# Sch_Master_Screen.net
KiCad netlist of a schematic drawn in Altium Designer
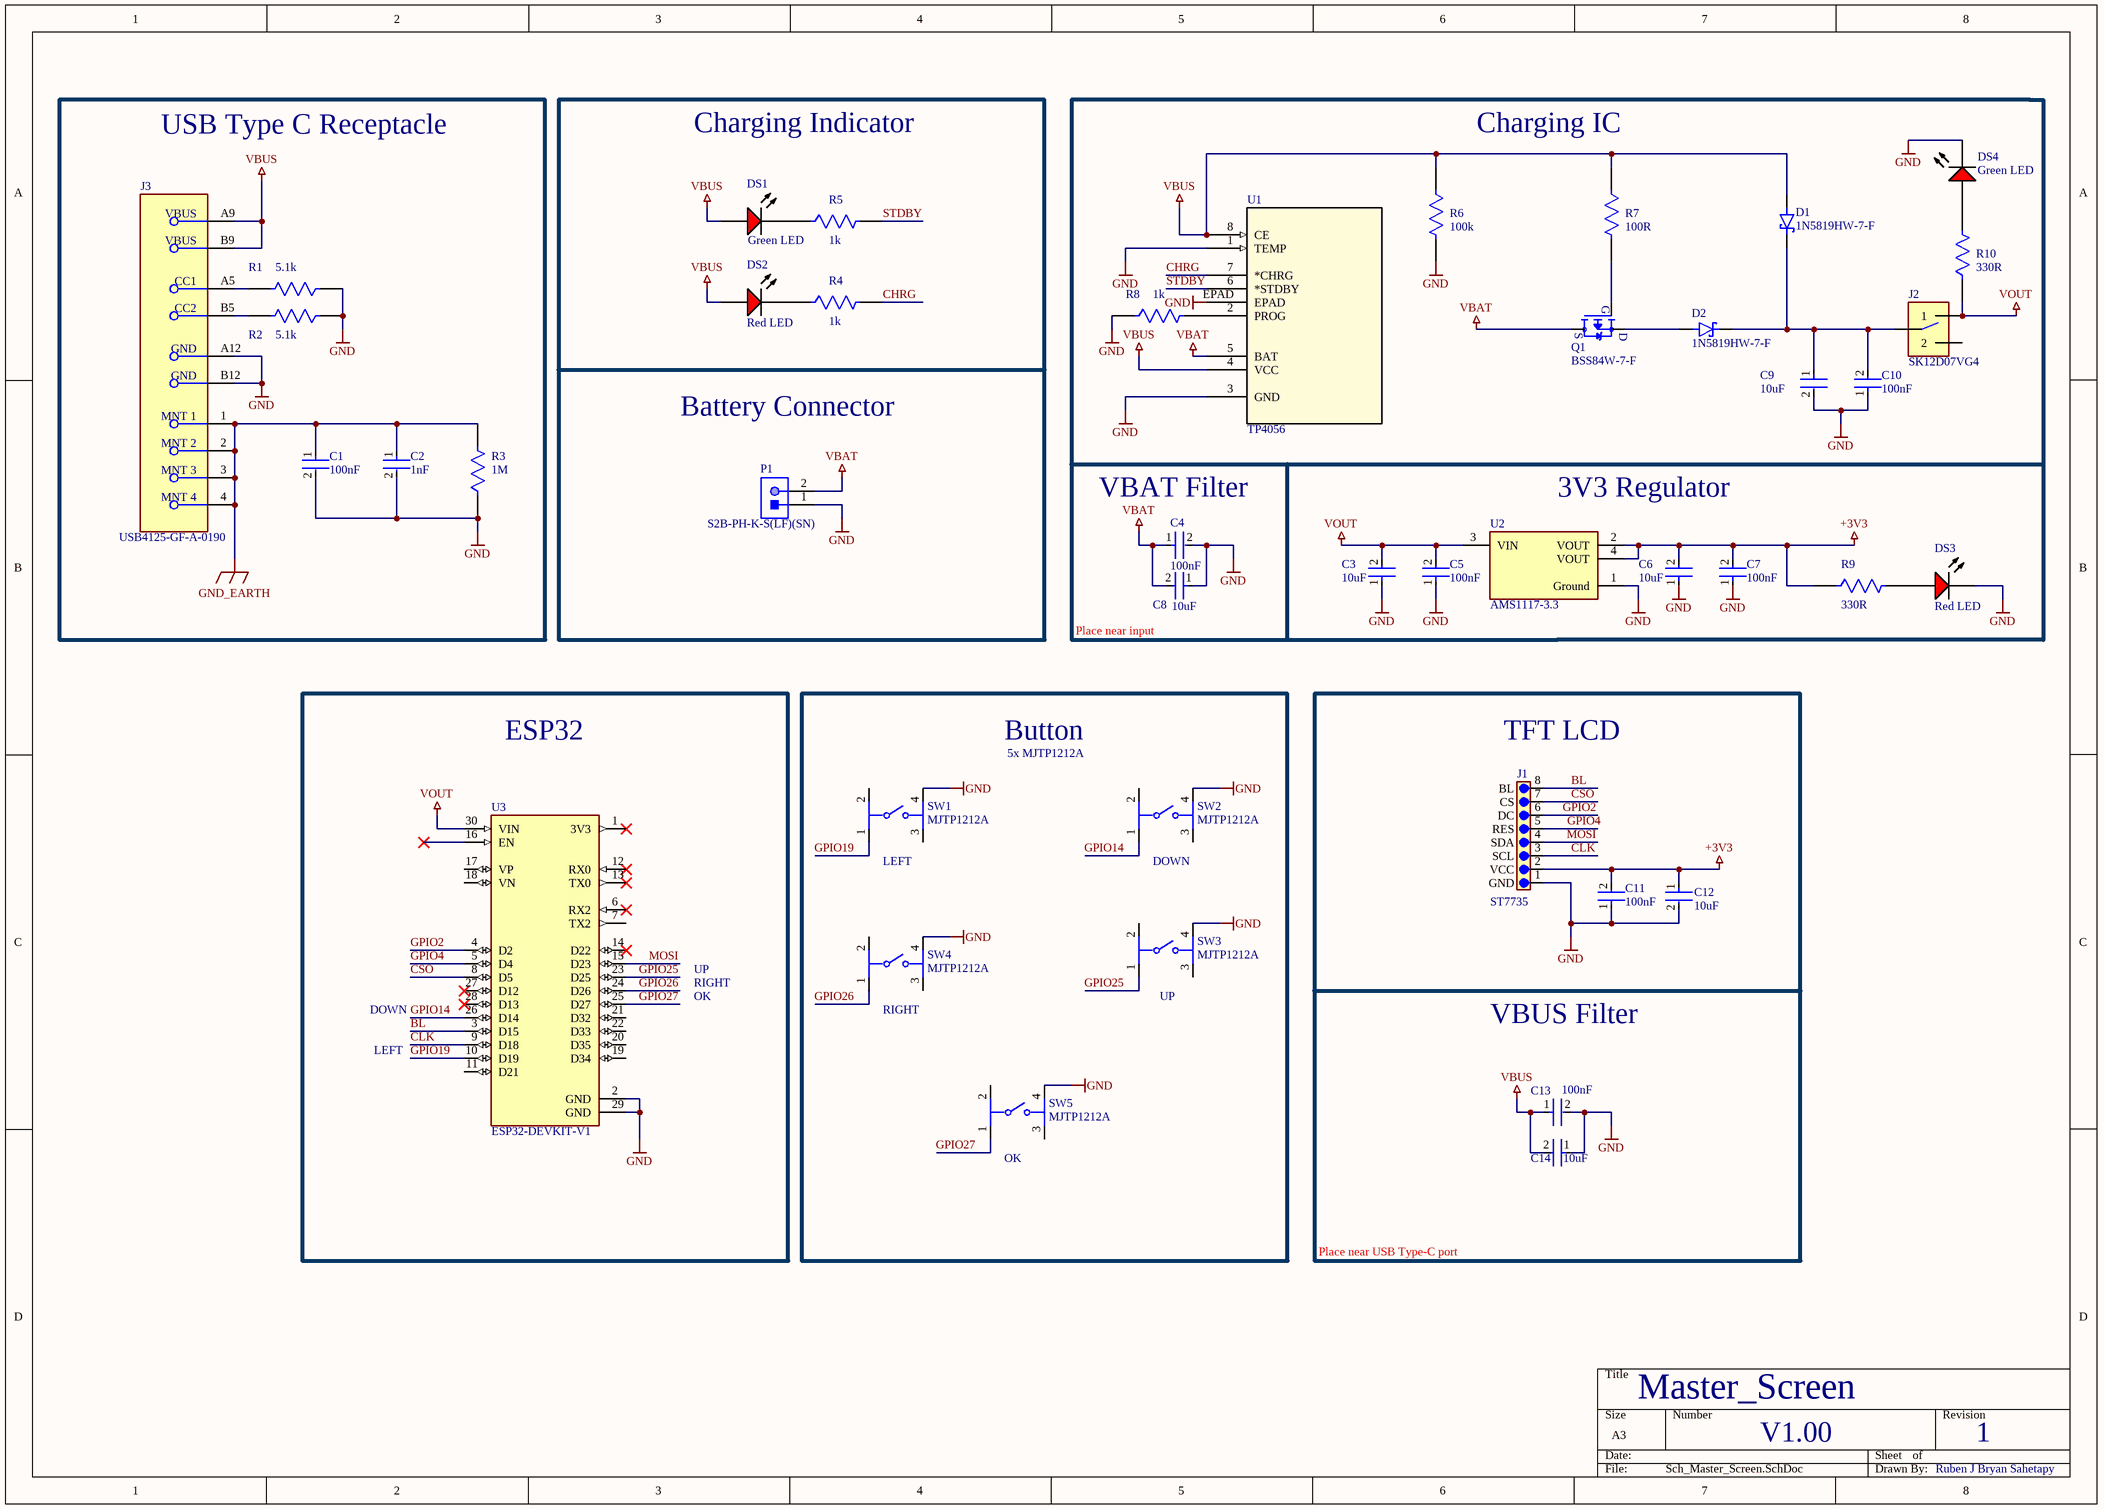
[diagram p0: Sch_Master_Screen.SchDoc]

(export (version "E")
  (design (tool "Eeschema 10.0.6"))
  (components
    (comp (ref "C1")
      (value "100nF")
      (footprint "FP-CC0805-0_85-MFG")
      (description "CAP CER 0.1UF 16V X7R 0805")
      (fields
        (field (name "MANUFACTURER PART NUMBER") "CC0805KRX7R7BB104")
        (field (name "MANUFACTURER") "Yageo")
      )
      (libsource (lib "Altium Content Vault") (part "11868f565c42a9108669ba33697ecf6"))
    )
    (comp (ref "C2")
      (value "1nF")
      (footprint "FP-CC0805-0_85-MFG")
      (description "CAP CER 0.1UF 16V X7R 0805")
      (fields
        (field (name "MANUFACTURER PART NUMBER") "CC0805KRX7R7BB104")
        (field (name "MANUFACTURER") "Yageo")
      )
      (libsource (lib "Altium Content Vault") (part "11868f565c42a9108669ba33697ecf6"))
    )
    (comp (ref "C3")
      (value "10uF")
      (footprint "FP-CC0805-0_85-MFG")
      (description "CAP CER 0.1UF 16V X7R 0805")
      (fields
        (field (name "MANUFACTURER PART NUMBER") "CC0805KRX7R7BB104")
        (field (name "MANUFACTURER") "Yageo")
      )
      (libsource (lib "Altium Content Vault") (part "11868f565c42a9108669ba33697ecf6"))
    )
    (comp (ref "C4")
      (value "100nF")
      (footprint "FP-CC0805-0_85-MFG")
      (description "CAP CER 0.1UF 16V X7R 0805")
      (fields
        (field (name "MANUFACTURER PART NUMBER") "CC0805KRX7R7BB104")
        (field (name "MANUFACTURER") "Yageo")
      )
      (libsource (lib "Altium Content Vault") (part "11868f565c42a9108669ba33697ecf6"))
    )
    (comp (ref "C5")
      (value "100nF")
      (footprint "FP-CC0805-0_85-MFG")
      (description "CAP CER 0.1UF 16V X7R 0805")
      (fields
        (field (name "MANUFACTURER PART NUMBER") "CC0805KRX7R7BB104")
        (field (name "MANUFACTURER") "Yageo")
      )
      (libsource (lib "Altium Content Vault") (part "11868f565c42a9108669ba33697ecf6"))
    )
    (comp (ref "C6")
      (value "10uF")
      (footprint "FP-CC0805-0_85-MFG")
      (description "CAP CER 0.1UF 16V X7R 0805")
      (fields
        (field (name "MANUFACTURER PART NUMBER") "CC0805KRX7R7BB104")
        (field (name "MANUFACTURER") "Yageo")
      )
      (libsource (lib "Altium Content Vault") (part "11868f565c42a9108669ba33697ecf6"))
    )
    (comp (ref "C7")
      (value "100nF")
      (footprint "FP-CC0805-0_85-MFG")
      (description "CAP CER 0.1UF 16V X7R 0805")
      (fields
        (field (name "MANUFACTURER PART NUMBER") "CC0805KRX7R7BB104")
        (field (name "MANUFACTURER") "Yageo")
      )
      (libsource (lib "Altium Content Vault") (part "11868f565c42a9108669ba33697ecf6"))
    )
    (comp (ref "C8")
      (value "10uF")
      (footprint "FP-CC0805-0_85-MFG")
      (description "CAP CER 0.1UF 16V X7R 0805")
      (fields
        (field (name "MANUFACTURER PART NUMBER") "CC0805KRX7R7BB104")
        (field (name "MANUFACTURER") "Yageo")
      )
      (libsource (lib "Altium Content Vault") (part "11868f565c42a9108669ba33697ecf6"))
    )
    (comp (ref "C9")
      (value "10uF")
      (footprint "FP-CC0805-0_85-MFG")
      (description "CAP CER 0.1UF 16V X7R 0805")
      (fields
        (field (name "MANUFACTURER PART NUMBER") "CC0805KRX7R7BB104")
        (field (name "MANUFACTURER") "Yageo")
      )
      (libsource (lib "Altium Content Vault") (part "11868f565c42a9108669ba33697ecf6"))
    )
    (comp (ref "C10")
      (value "100nF")
      (footprint "FP-CC0805-0_85-MFG")
      (description "CAP CER 0.1UF 16V X7R 0805")
      (fields
        (field (name "MANUFACTURER PART NUMBER") "CC0805KRX7R7BB104")
        (field (name "MANUFACTURER") "Yageo")
      )
      (libsource (lib "Altium Content Vault") (part "11868f565c42a9108669ba33697ecf6"))
    )
    (comp (ref "C11")
      (value "100nF")
      (footprint "FP-CC0805-0_85-MFG")
      (description "CAP CER 0.1UF 16V X7R 0805")
      (fields
        (field (name "MANUFACTURER PART NUMBER") "CC0805KRX7R7BB104")
        (field (name "MANUFACTURER") "Yageo")
      )
      (libsource (lib "Altium Content Vault") (part "11868f565c42a9108669ba33697ecf6"))
    )
    (comp (ref "C12")
      (value "10uF")
      (footprint "FP-CC0805-0_85-MFG")
      (description "CAP CER 0.1UF 16V X7R 0805")
      (fields
        (field (name "MANUFACTURER PART NUMBER") "CC0805KRX7R7BB104")
        (field (name "MANUFACTURER") "Yageo")
      )
      (libsource (lib "Altium Content Vault") (part "11868f565c42a9108669ba33697ecf6"))
    )
    (comp (ref "C13")
      (value "100nF")
      (footprint "FP-CC0805-0_85-MFG")
      (description "CAP CER 0.1UF 16V X7R 0805")
      (fields
        (field (name "MANUFACTURER PART NUMBER") "CC0805KRX7R7BB104")
        (field (name "MANUFACTURER") "Yageo")
      )
      (libsource (lib "Altium Content Vault") (part "11868f565c42a9108669ba33697ecf6"))
    )
    (comp (ref "C14")
      (value "10uF")
      (footprint "FP-CC0805-0_85-MFG")
      (description "CAP CER 0.1UF 16V X7R 0805")
      (fields
        (field (name "MANUFACTURER PART NUMBER") "CC0805KRX7R7BB104")
        (field (name "MANUFACTURER") "Yageo")
      )
      (libsource (lib "Altium Content Vault") (part "11868f565c42a9108669ba33697ecf6"))
    )
    (comp (ref "D1")
      (value "1N5819HW-7-F")
      (footprint "SOD3715X145N")
      (description "Schottky Diodes & Rectifiers SOD-123")
      (fields (field (name "MF") "Diodes Inc."))
      (libsource (lib "MarbleLib") (part "1N5819HW-7-F"))
    )
    (comp (ref "D2")
      (value "1N5819HW-7-F")
      (footprint "SOD3715X145N")
      (description "Schottky Diodes & Rectifiers SOD-123")
      (fields (field (name "MF") "Diodes Inc."))
      (libsource (lib "MarbleLib") (part "1N5819HW-7-F"))
    )
    (comp (ref "DS1")
      (value "Green LED")
      (footprint "LUMX-SML-LX1206IC_V")
      (description "LED Red, 65 mW, -40 to 85 degC, 2-Pin SMD, RoHS, Tape and Reel")
      (fields (field (name "MANUFACTURER") "Lumex") (field (name "PART NO") "SML-LX1206IC-TR"))
      (libsource (lib "Altium Content Vault") (part "LED-RED-AK-2"))
    )
    (comp (ref "DS2")
      (value "Red LED")
      (footprint "LUMX-SML-LX1206IC_V")
      (description "LED Red, 65 mW, -40 to 85 degC, 2-Pin SMD, RoHS, Tape and Reel")
      (fields (field (name "MANUFACTURER") "Lumex") (field (name "PART NO") "SML-LX1206IC-TR"))
      (libsource (lib "Altium Content Vault") (part "LED-RED-AK-2"))
    )
    (comp (ref "DS3")
      (value "Red LED")
      (footprint "LUMX-SML-LX1206IC_V")
      (description "LED Red, 65 mW, -40 to 85 degC, 2-Pin SMD, RoHS, Tape and Reel")
      (fields (field (name "MANUFACTURER") "Lumex") (field (name "PART NO") "SML-LX1206IC-TR"))
      (libsource (lib "Altium Content Vault") (part "LED-RED-AK-2"))
    )
    (comp (ref "DS4")
      (value "Green LED")
      (footprint "LUMX-SML-LX1206IC_V")
      (description "LED Red, 65 mW, -40 to 85 degC, 2-Pin SMD, RoHS, Tape and Reel")
      (fields (field (name "MANUFACTURER") "Lumex") (field (name "PART NO") "SML-LX1206IC-TR"))
      (libsource (lib "Altium Content Vault") (part "LED-RED-AK-2"))
    )
    (comp (ref "J1")
      (value "ST7735")
      (footprint "ST7735")
      (description "1.8 inches 128x160 RGB TFT LCD - ST7735 DRIVER")
      (fields (field (name "PART NUMBER") "TFT-ST7735"))
      (libsource (lib "MarbleLib") (part "ST7735"))
    )
    (comp (ref "J2")
      (value "SK12D07VG4")
      (footprint "SK12D07VG4")
      (description "Slide Switches - Side Knob")
      (fields (field (name "MF") "C&K"))
      (libsource (lib "MarbleLib") (part "SK12D07VG4"))
    )
    (comp (ref "J3")
      (value "USB4125-GF-A-0190")
      (footprint "FP-USB4125-GF-A-0190-MFG")
      (description "CONN RCPT TYPE C 6P SMD RA")
      (libsource (lib "Altium Content Vault") (part "a055484d46e58b234844902c9fd883a"))
    )
    (comp (ref "P1")
      (value "S2B-PH-K-S(LF)(SN)")
      (footprint "JST-S2B-PH-K-S_V")
      (fields (field (name "TOLERANCE") "20%"))
      (libsource (lib "Altium Content Vault") (part "CN-1P-M-R2"))
    )
    (comp (ref "Q1")
      (value "BSS84W-7-F")
      (footprint "SOT65P222X110-3N")
      (description "MOSFET P-Channel 50V 130MA SOT323")
      (fields (field (name "MF") "Diodes Inc."))
      (libsource (lib "MarbleLib") (part "BSS84W-7-F"))
    )
    (comp (ref "R1")
      (value "5.1k")
      (footprint "FP-RC1206-MFG")
      (description "RES SMD 0 OHM JUMPER 1/4W 1206")
      (fields
        (field (name "MANUFACTURER PART NUMBER") "RC1206JR-070RL")
        (field (name "MANUFACTURER") "YAGEO")
      )
      (libsource (lib "Altium Content Vault") (part "1029c3af85768c4190bb7ad29bc67b5"))
    )
    (comp (ref "R2")
      (value "5.1k")
      (footprint "FP-RC1206-MFG")
      (description "RES SMD 0 OHM JUMPER 1/4W 1206")
      (fields
        (field (name "MANUFACTURER PART NUMBER") "RC1206JR-070RL")
        (field (name "MANUFACTURER") "YAGEO")
      )
      (libsource (lib "Altium Content Vault") (part "1029c3af85768c4190bb7ad29bc67b5"))
    )
    (comp (ref "R3")
      (value "1M")
      (footprint "FP-RC1206-MFG")
      (description "RES SMD 0 OHM JUMPER 1/4W 1206")
      (fields
        (field (name "MANUFACTURER PART NUMBER") "RC1206JR-070RL")
        (field (name "MANUFACTURER") "YAGEO")
      )
      (libsource (lib "Altium Content Vault") (part "1029c3af85768c4190bb7ad29bc67b5"))
    )
    (comp (ref "R4")
      (value "1k")
      (footprint "FP-RC1206-MFG")
      (description "RES SMD 0 OHM JUMPER 1/4W 1206")
      (fields
        (field (name "MANUFACTURER PART NUMBER") "RC1206JR-070RL")
        (field (name "MANUFACTURER") "YAGEO")
      )
      (libsource (lib "Altium Content Vault") (part "1029c3af85768c4190bb7ad29bc67b5"))
    )
    (comp (ref "R5")
      (value "1k")
      (footprint "FP-RC1206-MFG")
      (description "RES SMD 0 OHM JUMPER 1/4W 1206")
      (fields
        (field (name "MANUFACTURER PART NUMBER") "RC1206JR-070RL")
        (field (name "MANUFACTURER") "YAGEO")
      )
      (libsource (lib "Altium Content Vault") (part "1029c3af85768c4190bb7ad29bc67b5"))
    )
    (comp (ref "R6")
      (value "100k")
      (footprint "FP-RC1206-MFG")
      (description "RES SMD 0 OHM JUMPER 1/4W 1206")
      (fields
        (field (name "MANUFACTURER PART NUMBER") "RC1206JR-070RL")
        (field (name "MANUFACTURER") "YAGEO")
      )
      (libsource (lib "Altium Content Vault") (part "1029c3af85768c4190bb7ad29bc67b5"))
    )
    (comp (ref "R7")
      (value "100R")
      (footprint "FP-RC1206-MFG")
      (description "RES SMD 0 OHM JUMPER 1/4W 1206")
      (fields
        (field (name "MANUFACTURER PART NUMBER") "RC1206JR-070RL")
        (field (name "MANUFACTURER") "YAGEO")
      )
      (libsource (lib "Altium Content Vault") (part "1029c3af85768c4190bb7ad29bc67b5"))
    )
    (comp (ref "R8")
      (value "1k")
      (footprint "FP-RC1206-MFG")
      (description "RES SMD 0 OHM JUMPER 1/4W 1206")
      (fields
        (field (name "MANUFACTURER PART NUMBER") "RC1206JR-070RL")
        (field (name "MANUFACTURER") "YAGEO")
      )
      (libsource (lib "Altium Content Vault") (part "1029c3af85768c4190bb7ad29bc67b5"))
    )
    (comp (ref "R9")
      (value "330R")
      (footprint "FP-RC1206-MFG")
      (description "RES SMD 0 OHM JUMPER 1/4W 1206")
      (fields
        (field (name "MANUFACTURER PART NUMBER") "RC1206JR-070RL")
        (field (name "MANUFACTURER") "YAGEO")
      )
      (libsource (lib "Altium Content Vault") (part "1029c3af85768c4190bb7ad29bc67b5"))
    )
    (comp (ref "R10")
      (value "330R")
      (footprint "FP-RC1206-MFG")
      (description "RES SMD 0 OHM JUMPER 1/4W 1206")
      (fields
        (field (name "MANUFACTURER PART NUMBER") "RC1206JR-070RL")
        (field (name "MANUFACTURER") "YAGEO")
      )
      (libsource (lib "Altium Content Vault") (part "1029c3af85768c4190bb7ad29bc67b5"))
    )
    (comp (ref "SW1")
      (value "MJTP1212A")
      (footprint "FP-MJTP1212A-MFG")
      (description "Switch Tactile Button 12x12mm")
      (libsource (lib "MarbleLib") (part "CMP-47024-000003-1"))
    )
    (comp (ref "SW2")
      (value "MJTP1212A")
      (footprint "FP-MJTP1212A-MFG")
      (description "Switch Tactile Button 12x12mm")
      (libsource (lib "MarbleLib") (part "CMP-47024-000003-1"))
    )
    (comp (ref "SW3")
      (value "MJTP1212A")
      (footprint "FP-MJTP1212A-MFG")
      (description "Switch Tactile Button 12x12mm")
      (libsource (lib "MarbleLib") (part "CMP-47024-000003-1"))
    )
    (comp (ref "SW4")
      (value "MJTP1212A")
      (footprint "FP-MJTP1212A-MFG")
      (description "Switch Tactile Button 12x12mm")
      (libsource (lib "MarbleLib") (part "CMP-47024-000003-1"))
    )
    (comp (ref "SW5")
      (value "MJTP1212A")
      (footprint "FP-MJTP1212A-MFG")
      (description "Switch Tactile Button 12x12mm")
      (libsource (lib "MarbleLib") (part "CMP-47024-000003-1"))
    )
    (comp (ref "U1")
      (value "TP4056")
      (footprint "SOP8-PP_TPW")
      (description "charger for single cell lithium-ion batteries")
      (fields (field (name "COPYRIGHT") "Copyright (C) 2025 Ultra Librarian. All rights reserved."))
      (libsource (lib "MarbleLib") (part "TP4056"))
    )
    (comp (ref "U2")
      (value "AMS1117-3.3")
      (footprint "FP-AMS1117-IPC_C")
      (description "LDO Voltage Regulators 1A, 3.3V")
      (fields
        (field (name "OCTOPART") "https://octopart.com/ams1117-3.3-advanced+monolithic+systems-25899300")
        (field (name "MANUFACTURER") "Advanced Monolithic Systems")
      )
      (libsource (lib "Altium Content Vault") (part "8bdbb5f8e77002000e30dd2845d0354"))
    )
    (comp (ref "U3")
      (value "ESP32-DEVKIT-V1")
      (footprint "MODULE_ESP32_DEVKIT_V1")
      (description "ESP32-DEVKIT-V1 30 Pins")
      (fields (field (name "MF") "Do it"))
      (libsource (lib "MarbleLib") (part "ESP32-DEVKIT-V1"))
    )
  )
  (nets
    (net (code "1") (name "+3V3") (class "Default")
      (node (ref "C11") (pin "2") (pinfunction "2_2") (pintype "passive"))
      (node (ref "C12") (pin "1") (pinfunction "1_1") (pintype "passive"))
      (node (ref "C6") (pin "2") (pinfunction "2_2") (pintype "passive"))
      (node (ref "C7") (pin "2") (pinfunction "2_2") (pintype "passive"))
      (node (ref "J1") (pin "2") (pinfunction "VCC_2") (pintype "passive"))
      (node (ref "R9") (pin "1") (pinfunction "1_1") (pintype "passive"))
      (node (ref "U2") (pin "2") (pinfunction "VOUT_2") (pintype "passive"))
      (node (ref "U2") (pin "4") (pinfunction "VOUT_4") (pintype "passive"))
    )
    (net (code "2") (name "/BL") (class "Default")
      (node (ref "J1") (pin "8") (pinfunction "BL_8") (pintype "passive"))
      (node (ref "U3") (pin "3") (pinfunction "D15_3") (pintype "bidirectional"))
    )
    (net (code "3") (name "/CHRG") (class "Default")
      (node (ref "R4") (pin "2") (pinfunction "2_2") (pintype "passive"))
      (node (ref "U1") (pin "7") (pinfunction "*CHRG_7") (pintype "passive"))
    )
    (net (code "4") (name "/CLK") (class "Default")
      (node (ref "J1") (pin "3") (pinfunction "SCL_3") (pintype "passive"))
      (node (ref "U3") (pin "9") (pinfunction "D18_9") (pintype "bidirectional"))
    )
    (net (code "5") (name "/CSO") (class "Default")
      (node (ref "J1") (pin "7") (pinfunction "CS_7") (pintype "passive"))
      (node (ref "U3") (pin "8") (pinfunction "D5_8") (pintype "bidirectional"))
    )
    (net (code "6") (name "/GPIO2") (class "Default")
      (node (ref "J1") (pin "6") (pinfunction "DC_6") (pintype "passive"))
      (node (ref "U3") (pin "4") (pinfunction "D2_4") (pintype "bidirectional"))
    )
    (net (code "7") (name "/GPIO4") (class "Default")
      (node (ref "J1") (pin "5") (pinfunction "RES_5") (pintype "passive"))
      (node (ref "U3") (pin "5") (pinfunction "D4_5") (pintype "bidirectional"))
    )
    (net (code "8") (name "/GPIO14") (class "Default")
      (node (ref "SW2") (pin "1") (pinfunction "1_1") (pintype "passive"))
      (node (ref "U3") (pin "26") (pinfunction "D14_26") (pintype "bidirectional"))
    )
    (net (code "9") (name "/GPIO19") (class "Default")
      (node (ref "SW1") (pin "1") (pinfunction "1_1") (pintype "passive"))
      (node (ref "U3") (pin "10") (pinfunction "D19_10") (pintype "bidirectional"))
    )
    (net (code "10") (name "/GPIO25") (class "Default")
      (node (ref "SW3") (pin "1") (pinfunction "1_1") (pintype "passive"))
      (node (ref "U3") (pin "23") (pinfunction "D25_23") (pintype "bidirectional"))
    )
    (net (code "11") (name "/GPIO26") (class "Default")
      (node (ref "SW4") (pin "1") (pinfunction "1_1") (pintype "passive"))
      (node (ref "U3") (pin "24") (pinfunction "D26_24") (pintype "bidirectional"))
    )
    (net (code "12") (name "/GPIO27") (class "Default")
      (node (ref "SW5") (pin "1") (pinfunction "1_1") (pintype "passive"))
      (node (ref "U3") (pin "25") (pinfunction "D27_25") (pintype "bidirectional"))
    )
    (net (code "13") (name "/MOSI") (class "Default")
      (node (ref "J1") (pin "4") (pinfunction "SDA_4") (pintype "passive"))
      (node (ref "U3") (pin "15") (pinfunction "D23_15") (pintype "bidirectional"))
    )
    (net (code "14") (name "/STDBY") (class "Default")
      (node (ref "R5") (pin "2") (pinfunction "2_2") (pintype "passive"))
      (node (ref "U1") (pin "6") (pinfunction "*STDBY_6") (pintype "passive"))
    )
    (net (code "15") (name "GND") (class "Default")
      (node (ref "C1") (pin "2") (pinfunction "2_2") (pintype "passive"))
      (node (ref "C10") (pin "1") (pinfunction "1_1") (pintype "passive"))
      (node (ref "C11") (pin "1") (pinfunction "1_1") (pintype "passive"))
      (node (ref "C12") (pin "2") (pinfunction "2_2") (pintype "passive"))
      (node (ref "C13") (pin "2") (pinfunction "2_2") (pintype "passive"))
      (node (ref "C14") (pin "1") (pinfunction "1_1") (pintype "passive"))
      (node (ref "C2") (pin "2") (pinfunction "2_2") (pintype "passive"))
      (node (ref "C3") (pin "1") (pinfunction "1_1") (pintype "passive"))
      (node (ref "C4") (pin "2") (pinfunction "2_2") (pintype "passive"))
      (node (ref "C5") (pin "1") (pinfunction "1_1") (pintype "passive"))
      (node (ref "C6") (pin "1") (pinfunction "1_1") (pintype "passive"))
      (node (ref "C7") (pin "1") (pinfunction "1_1") (pintype "passive"))
      (node (ref "C8") (pin "1") (pinfunction "1_1") (pintype "passive"))
      (node (ref "C9") (pin "2") (pinfunction "2_2") (pintype "passive"))
      (node (ref "DS3") (pin "2") (pinfunction "K_2") (pintype "passive"))
      (node (ref "DS4") (pin "2") (pinfunction "K_2") (pintype "passive"))
      (node (ref "J1") (pin "1") (pinfunction "GND_1") (pintype "passive"))
      (node (ref "J3") (pin "A12") (pinfunction "GND_A12") (pintype "passive"))
      (node (ref "J3") (pin "B12") (pinfunction "GND_B12") (pintype "passive"))
      (node (ref "P1") (pin "1") (pinfunction "1_1") (pintype "passive"))
      (node (ref "R1") (pin "1") (pinfunction "1_1") (pintype "passive"))
      (node (ref "R2") (pin "1") (pinfunction "1_1") (pintype "passive"))
      (node (ref "R3") (pin "1") (pinfunction "1_1") (pintype "passive"))
      (node (ref "R6") (pin "2") (pinfunction "2_2") (pintype "passive"))
      (node (ref "R8") (pin "1") (pinfunction "1_1") (pintype "passive"))
      (node (ref "SW1") (pin "4") (pinfunction "4_4") (pintype "passive"))
      (node (ref "SW2") (pin "4") (pinfunction "4_4") (pintype "passive"))
      (node (ref "SW3") (pin "4") (pinfunction "4_4") (pintype "passive"))
      (node (ref "SW4") (pin "4") (pinfunction "4_4") (pintype "passive"))
      (node (ref "SW5") (pin "4") (pinfunction "4_4") (pintype "passive"))
      (node (ref "U1") (pin "1") (pinfunction "TEMP_1") (pintype "input"))
      (node (ref "U1") (pin "3") (pinfunction "GND_3") (pintype "power_in"))
      (node (ref "U1") (pin "EPAD") (pinfunction "EPAD_EPAD") (pintype "passive"))
      (node (ref "U2") (pin "1") (pinfunction "Ground_1") (pintype "power_in"))
      (node (ref "U3") (pin "2") (pinfunction "GND_2") (pintype "power_in"))
      (node (ref "U3") (pin "29") (pinfunction "GND_29") (pintype "power_in"))
    )
    (net (code "16") (name "GND_EARTH") (class "Default")
      (node (ref "C1") (pin "1") (pinfunction "1_1") (pintype "passive"))
      (node (ref "C2") (pin "1") (pinfunction "1_1") (pintype "passive"))
      (node (ref "J3") (pin "1") (pinfunction "MNT_1_1") (pintype "passive"))
      (node (ref "J3") (pin "2") (pinfunction "MNT_2_2") (pintype "passive"))
      (node (ref "J3") (pin "3") (pinfunction "MNT_3_3") (pintype "passive"))
      (node (ref "J3") (pin "4") (pinfunction "MNT_4_4") (pintype "passive"))
      (node (ref "R3") (pin "2") (pinfunction "2_2") (pintype "passive"))
    )
    (net (code "17") (name "Net-(D1-K)") (class "Default")
      (node (ref "C10") (pin "2") (pinfunction "2_2") (pintype "passive"))
      (node (ref "C9") (pin "1") (pinfunction "1_1") (pintype "passive"))
      (node (ref "D1") (pin "C") (pinfunction "K_C") (pintype "passive"))
      (node (ref "D2") (pin "C") (pinfunction "K_C") (pintype "passive"))
      (node (ref "J2") (pin "COM") (pinfunction "COM_COM") (pintype "passive"))
    )
    (net (code "18") (name "Net-(DS1-K)") (class "Default")
      (node (ref "DS1") (pin "2") (pinfunction "K_2") (pintype "passive"))
      (node (ref "R5") (pin "1") (pinfunction "1_1") (pintype "passive"))
    )
    (net (code "19") (name "Net-(DS2-K)") (class "Default")
      (node (ref "DS2") (pin "2") (pinfunction "K_2") (pintype "passive"))
      (node (ref "R4") (pin "1") (pinfunction "1_1") (pintype "passive"))
    )
    (net (code "20") (name "Net-(DS3-A)") (class "Default")
      (node (ref "DS3") (pin "1") (pinfunction "A_1") (pintype "passive"))
      (node (ref "R9") (pin "2") (pinfunction "2_2") (pintype "passive"))
    )
    (net (code "21") (name "Net-(DS4-A)") (class "Default")
      (node (ref "DS4") (pin "1") (pinfunction "A_1") (pintype "passive"))
      (node (ref "R10") (pin "2") (pinfunction "2_2") (pintype "passive"))
    )
    (net (code "22") (name "Net-(J3-CC1)") (class "Default")
      (node (ref "J3") (pin "A5") (pinfunction "CC1_A5") (pintype "passive"))
      (node (ref "R1") (pin "2") (pinfunction "2_2") (pintype "passive"))
    )
    (net (code "23") (name "Net-(J3-CC2)") (class "Default")
      (node (ref "J3") (pin "B5") (pinfunction "CC2_B5") (pintype "passive"))
      (node (ref "R2") (pin "2") (pinfunction "2_2") (pintype "passive"))
    )
    (net (code "24") (name "Net-(Q1-G)") (class "Default")
      (node (ref "Q1") (pin "1") (pinfunction "G_1") (pintype "passive"))
      (node (ref "R7") (pin "2") (pinfunction "2_2") (pintype "passive"))
    )
    (net (code "25") (name "Net-(Q1-S)") (class "Default")
      (node (ref "D2") (pin "A") (pinfunction "A_A") (pintype "passive"))
      (node (ref "Q1") (pin "2") (pinfunction "S_2") (pintype "passive"))
    )
    (net (code "26") (name "Net-(U1-PROG)") (class "Default")
      (node (ref "R8") (pin "2") (pinfunction "2_2") (pintype "passive"))
      (node (ref "U1") (pin "2") (pinfunction "PROG_2") (pintype "passive"))
    )
    (net (code "27") (name "VBAT") (class "Default")
      (node (ref "C4") (pin "1") (pinfunction "1_1") (pintype "passive"))
      (node (ref "C8") (pin "2") (pinfunction "2_2") (pintype "passive"))
      (node (ref "P1") (pin "2") (pinfunction "2_2") (pintype "passive"))
      (node (ref "Q1") (pin "3") (pinfunction "D_3") (pintype "passive"))
      (node (ref "U1") (pin "5") (pinfunction "BAT_5") (pintype "power_in"))
    )
    (net (code "28") (name "VBUS") (class "Default")
      (node (ref "C13") (pin "1") (pinfunction "1_1") (pintype "passive"))
      (node (ref "C14") (pin "2") (pinfunction "2_2") (pintype "passive"))
      (node (ref "D1") (pin "A") (pinfunction "A_A") (pintype "passive"))
      (node (ref "DS1") (pin "1") (pinfunction "A_1") (pintype "passive"))
      (node (ref "DS2") (pin "1") (pinfunction "A_1") (pintype "passive"))
      (node (ref "J3") (pin "A9") (pinfunction "VBUS_A9") (pintype "passive"))
      (node (ref "J3") (pin "B9") (pinfunction "VBUS_B9") (pintype "passive"))
      (node (ref "R6") (pin "1") (pinfunction "1_1") (pintype "passive"))
      (node (ref "R7") (pin "1") (pinfunction "1_1") (pintype "passive"))
      (node (ref "U1") (pin "4") (pinfunction "VCC_4") (pintype "power_in"))
      (node (ref "U1") (pin "8") (pinfunction "CE_8") (pintype "input"))
    )
    (net (code "29") (name "VOUT") (class "Default")
      (node (ref "C3") (pin "2") (pinfunction "2_2") (pintype "passive"))
      (node (ref "C5") (pin "2") (pinfunction "2_2") (pintype "passive"))
      (node (ref "J2") (pin "1") (pinfunction "1_1") (pintype "passive"))
      (node (ref "R10") (pin "1") (pinfunction "1_1") (pintype "passive"))
      (node (ref "U2") (pin "3") (pinfunction "VIN_3") (pintype "power_in"))
      (node (ref "U3") (pin "30") (pinfunction "VIN_30") (pintype "input"))
    )
    (net (code "30") (name "unconnected-(J2-Pad2)") (class "Default")
      (node (ref "J2") (pin "2") (pinfunction "2_2") (pintype "passive"))
    )
    (net (code "31") (name "unconnected-(SW1-Pad2)") (class "Default")
      (node (ref "SW1") (pin "2") (pinfunction "2_2") (pintype "passive"))
    )
    (net (code "32") (name "unconnected-(SW1-Pad3)") (class "Default")
      (node (ref "SW1") (pin "3") (pinfunction "3_3") (pintype "passive"))
    )
    (net (code "33") (name "unconnected-(SW2-Pad2)") (class "Default")
      (node (ref "SW2") (pin "2") (pinfunction "2_2") (pintype "passive"))
    )
    (net (code "34") (name "unconnected-(SW2-Pad3)") (class "Default")
      (node (ref "SW2") (pin "3") (pinfunction "3_3") (pintype "passive"))
    )
    (net (code "35") (name "unconnected-(SW3-Pad2)") (class "Default")
      (node (ref "SW3") (pin "2") (pinfunction "2_2") (pintype "passive"))
    )
    (net (code "36") (name "unconnected-(SW3-Pad3)") (class "Default")
      (node (ref "SW3") (pin "3") (pinfunction "3_3") (pintype "passive"))
    )
    (net (code "37") (name "unconnected-(SW4-Pad2)") (class "Default")
      (node (ref "SW4") (pin "2") (pinfunction "2_2") (pintype "passive"))
    )
    (net (code "38") (name "unconnected-(SW4-Pad3)") (class "Default")
      (node (ref "SW4") (pin "3") (pinfunction "3_3") (pintype "passive"))
    )
    (net (code "39") (name "unconnected-(SW5-Pad2)") (class "Default")
      (node (ref "SW5") (pin "2") (pinfunction "2_2") (pintype "passive"))
    )
    (net (code "40") (name "unconnected-(SW5-Pad3)") (class "Default")
      (node (ref "SW5") (pin "3") (pinfunction "3_3") (pintype "passive"))
    )
    (net (code "41") (name "unconnected-(U3-3V3-Pad1)") (class "Default")
      (node (ref "U3") (pin "1") (pinfunction "3V3_1") (pintype "output+no_connect"))
    )
    (net (code "42") (name "unconnected-(U3-D12-Pad27)") (class "Default")
      (node (ref "U3") (pin "27") (pinfunction "D12_27") (pintype "bidirectional+no_connect"))
    )
    (net (code "43") (name "unconnected-(U3-D13-Pad28)") (class "Default")
      (node (ref "U3") (pin "28") (pinfunction "D13_28") (pintype "bidirectional+no_connect"))
    )
    (net (code "44") (name "unconnected-(U3-D21-Pad11)") (class "Default")
      (node (ref "U3") (pin "11") (pinfunction "D21_11") (pintype "bidirectional"))
    )
    (net (code "45") (name "unconnected-(U3-D22-Pad14)") (class "Default")
      (node (ref "U3") (pin "14") (pinfunction "D22_14") (pintype "bidirectional+no_connect"))
    )
    (net (code "46") (name "unconnected-(U3-D32-Pad21)") (class "Default")
      (node (ref "U3") (pin "21") (pinfunction "D32_21") (pintype "bidirectional"))
    )
    (net (code "47") (name "unconnected-(U3-D33-Pad22)") (class "Default")
      (node (ref "U3") (pin "22") (pinfunction "D33_22") (pintype "bidirectional"))
    )
    (net (code "48") (name "unconnected-(U3-D34-Pad19)") (class "Default")
      (node (ref "U3") (pin "19") (pinfunction "D34_19") (pintype "bidirectional"))
    )
    (net (code "49") (name "unconnected-(U3-D35-Pad20)") (class "Default")
      (node (ref "U3") (pin "20") (pinfunction "D35_20") (pintype "bidirectional"))
    )
    (net (code "50") (name "unconnected-(U3-EN-Pad16)") (class "Default")
      (node (ref "U3") (pin "16") (pinfunction "EN_16") (pintype "input+no_connect"))
    )
    (net (code "51") (name "unconnected-(U3-RX0-Pad12)") (class "Default")
      (node (ref "U3") (pin "12") (pinfunction "RX0_12") (pintype "input+no_connect"))
    )
    (net (code "52") (name "unconnected-(U3-RX2-Pad6)") (class "Default")
      (node (ref "U3") (pin "6") (pinfunction "RX2_6") (pintype "input+no_connect"))
    )
    (net (code "53") (name "unconnected-(U3-TX0-Pad13)") (class "Default")
      (node (ref "U3") (pin "13") (pinfunction "TX0_13") (pintype "output+no_connect"))
    )
    (net (code "54") (name "unconnected-(U3-TX2-Pad7)") (class "Default")
      (node (ref "U3") (pin "7") (pinfunction "TX2_7") (pintype "output"))
    )
    (net (code "55") (name "unconnected-(U3-VN-Pad18)") (class "Default")
      (node (ref "U3") (pin "18") (pinfunction "VN_18") (pintype "bidirectional"))
    )
    (net (code "56") (name "unconnected-(U3-VP-Pad17)") (class "Default")
      (node (ref "U3") (pin "17") (pinfunction "VP_17") (pintype "bidirectional"))
    )
  )
)
